# SCH_Rubik_2024-01-09.net
KiCad netlist of a schematic drawn in EasyEDA
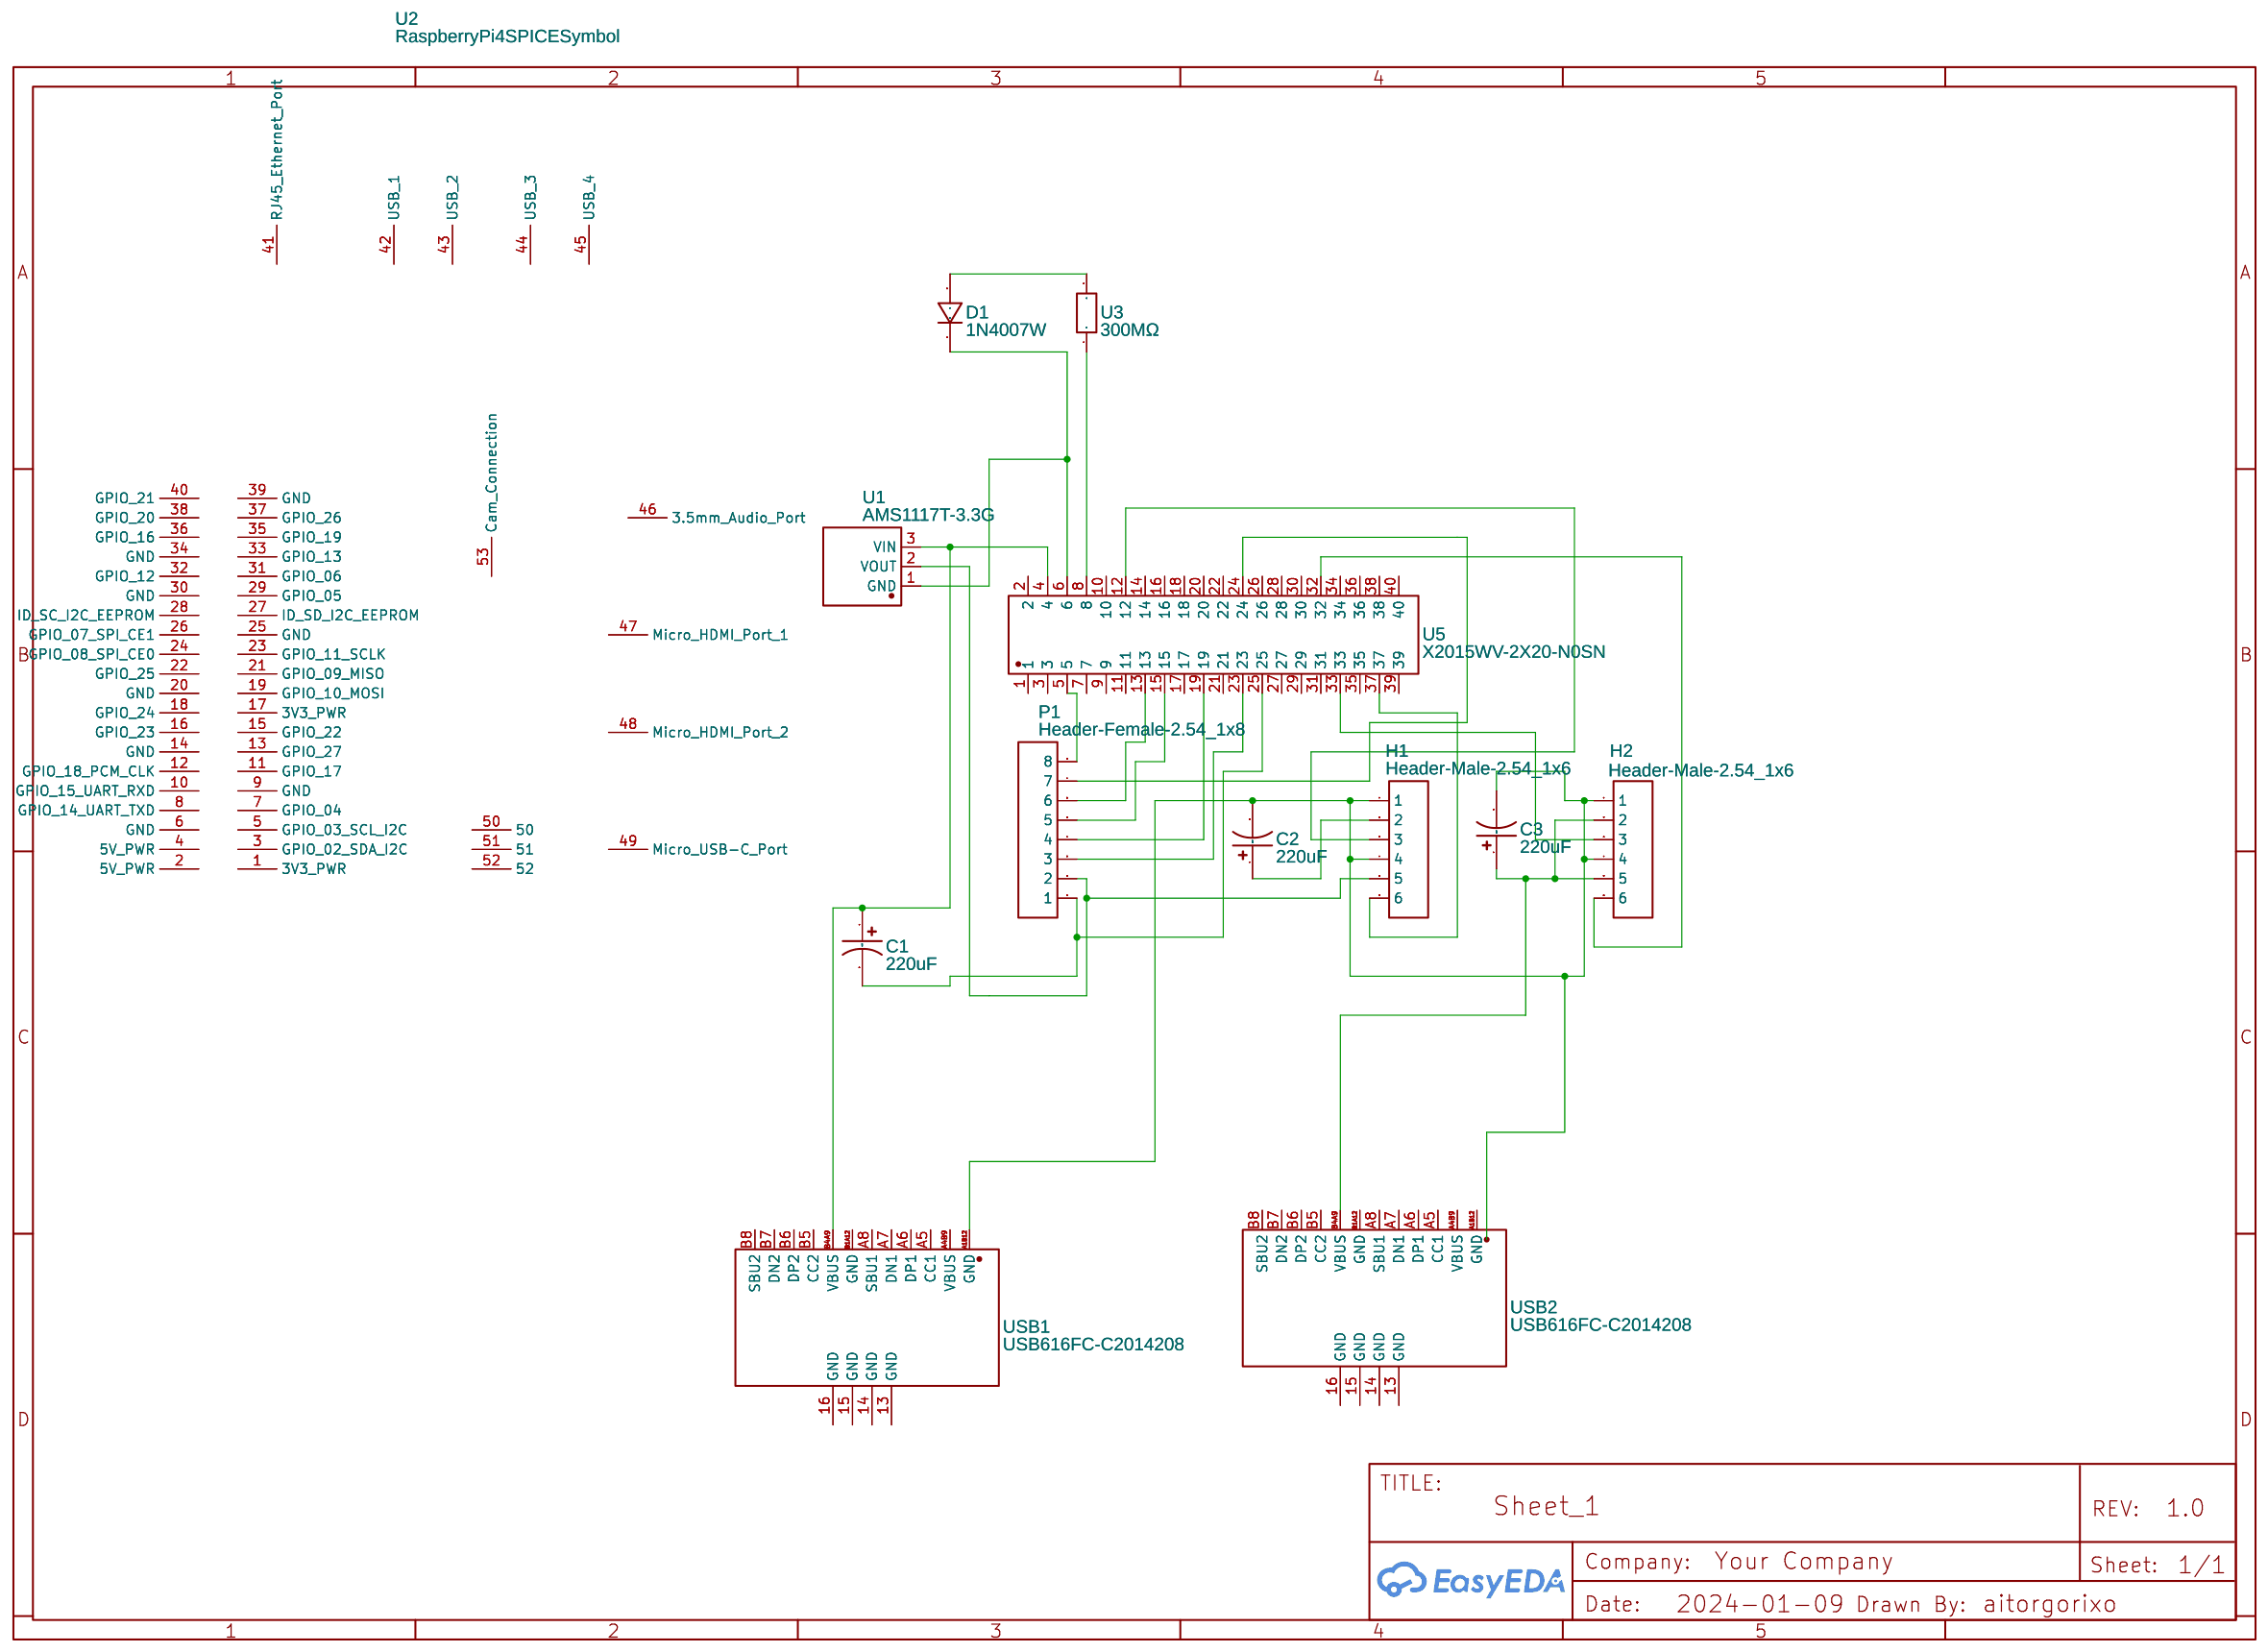
[diagram p0: schematic sheet]

(export (version "E")
  (design (tool "Eeschema 10.0.6"))
  (components
    (comp (ref "C1")
      (value "220uF")
      (fields
        (field (name "Manufacturer Part") "35YXG220MLLCT78X16")
        (field (name "Manufacturer") "rubycon(红宝石)")
      )
      (libsource (lib "") (part "35YXG220MLLCT78X16"))
    )
    (comp (ref "C2")
      (value "220uF")
      (fields
        (field (name "Manufacturer Part") "35YXG220MLLCT78X16")
        (field (name "Manufacturer") "rubycon(红宝石)")
      )
      (libsource (lib "") (part "35YXG220MLLCT78X16_1"))
    )
    (comp (ref "C3")
      (value "220uF")
      (fields
        (field (name "Manufacturer Part") "35YXG220MLLCT78X16")
        (field (name "Manufacturer") "rubycon(红宝石)")
      )
      (libsource (lib "") (part "35YXG220MLLCT78X16_1"))
    )
    (comp (ref "D1")
      (value "1N4007W")
      (fields (field (name "Manufacturer") "BLUE ROCKET"))
      (libsource (lib "") (part "1N4007W"))
    )
    (comp (ref "H1")
      (value "Header-Male-2.54_1x6")
      (fields (field (name "Manufacturer Part") "2.54-1x6P直针") (field (name "Manufacturer") "BOOMELE(博穆精密)"))
      (libsource (lib "") (part "Header-Male-2.54_1x6"))
    )
    (comp (ref "H2")
      (value "Header-Male-2.54_1x6")
      (fields (field (name "Manufacturer Part") "2.54-1x6P直针") (field (name "Manufacturer") "BOOMELE(博穆精密)"))
      (libsource (lib "") (part "Header-Male-2.54_1x6"))
    )
    (comp (ref "P1")
      (value "Header-Female-2.54_1x8")
      (fields (field (name "Manufacturer Part") "2.54-1*8P母环保") (field (name "Manufacturer") "BOOMELE(博穆精密)"))
      (libsource (lib "") (part "Header-Female-2.54_1x8"))
    )
    (comp (ref "U1")
      (value "AMS1117T-3.3G")
      (fields (field (name "Manufacturer") "HGC(深圳汉芯)"))
      (libsource (lib "") (part "AMS1117T-3.3G"))
    )
    (comp (ref "U2") (value "RaspberryPi4SPICESymbol") (libsource (lib "") (part "RaspberryPi4SPICESymbol")))
    (comp (ref "U3")
      (value "300MΩ")
      (fields
        (field (name "Manufacturer Part") "WW12JTR300")
        (field (name "Manufacturer") "SEI(Stackpole Electronics Inc.)")
      )
      (libsource (lib "") (part "WW12JTR300"))
    )
    (comp (ref "U5")
      (value "X2015WV-2X20-N0SN")
      (fields
        (field (name "Manufacturer Part") "X2015WV-2x20-46SN")
        (field (name "Manufacturer") "XKB Connectivity(中国星坤)")
      )
      (libsource (lib "") (part "X2015WV-2X20-N0SN"))
    )
    (comp (ref "USB1")
      (value "USB616FC-C2014208")
      (fields (field (name "Manufacturer") "ATOM(爱特姆)"))
      (libsource (lib "") (part "USB616FC-C2014208"))
    )
    (comp (ref "USB2")
      (value "USB616FC-C2014208")
      (fields (field (name "Manufacturer") "ATOM(爱特姆)"))
      (libsource (lib "") (part "USB616FC-C2014208"))
    )
  )
  (nets
    (net (code "1") (name "Net-(C1-Pad2)") (class "Default")
      (node (ref "C1") (pin "2") (pinfunction "2_2") (pintype "unspecified"))
      (node (ref "P1") (pin "1") (pinfunction "1_1") (pintype "input"))
      (node (ref "U5") (pin "25") (pinfunction "25_25") (pintype "unspecified"))
    )
    (net (code "2") (name "Net-(C2-Pad1)") (class "Default")
      (node (ref "C2") (pin "1") (pinfunction "1_1") (pintype "unspecified"))
      (node (ref "H1") (pin "2") (pinfunction "2_2") (pintype "input"))
    )
    (net (code "3") (name "Net-(C2-Pad2)") (class "Default")
      (node (ref "C2") (pin "2") (pinfunction "2_2") (pintype "unspecified"))
      (node (ref "C3") (pin "2") (pinfunction "2_2") (pintype "unspecified"))
      (node (ref "H1") (pin "1") (pinfunction "1_1") (pintype "input"))
      (node (ref "H1") (pin "4") (pinfunction "4_4") (pintype "input"))
      (node (ref "H2") (pin "1") (pinfunction "1_1") (pintype "input"))
      (node (ref "H2") (pin "4") (pinfunction "4_4") (pintype "input"))
      (node (ref "USB1") (pin "A1B12") (pinfunction "GND_A1B12") (pintype "unspecified"))
    )
    (net (code "4") (name "Net-(C3-Pad1)") (class "Default")
      (node (ref "C3") (pin "1") (pinfunction "1_1") (pintype "unspecified"))
      (node (ref "H2") (pin "2") (pinfunction "2_2") (pintype "input"))
      (node (ref "H2") (pin "5") (pinfunction "5_5") (pintype "input"))
      (node (ref "USB2") (pin "B4A9") (pinfunction "VBUS_B4A9") (pintype "unspecified"))
    )
    (net (code "5") (name "Net-(D1-Pad2)") (class "Default")
      (node (ref "D1") (pin "2") (pinfunction "2_2") (pintype "unspecified"))
      (node (ref "U3") (pin "2") (pinfunction "2_2") (pintype "unspecified"))
    )
    (net (code "6") (name "Net-(H1-Pad3)") (class "Default")
      (node (ref "H1") (pin "3") (pinfunction "3_3") (pintype "input"))
      (node (ref "U5") (pin "12") (pinfunction "12_12") (pintype "unspecified"))
    )
    (net (code "7") (name "Net-(H1-Pad6)") (class "Default")
      (node (ref "H1") (pin "6") (pinfunction "6_6") (pintype "input"))
      (node (ref "U5") (pin "37") (pinfunction "37_37") (pintype "unspecified"))
    )
    (net (code "8") (name "Net-(H2-Pad3)") (class "Default")
      (node (ref "H2") (pin "3") (pinfunction "3_3") (pintype "input"))
      (node (ref "U5") (pin "33") (pinfunction "33_33") (pintype "unspecified"))
    )
    (net (code "9") (name "Net-(H2-Pad6)") (class "Default")
      (node (ref "H2") (pin "6") (pinfunction "6_6") (pintype "input"))
      (node (ref "U5") (pin "32") (pinfunction "32_32") (pintype "unspecified"))
    )
    (net (code "10") (name "Net-(P1-Pad3)") (class "Default")
      (node (ref "P1") (pin "3") (pinfunction "3_3") (pintype "input"))
      (node (ref "U5") (pin "23") (pinfunction "23_23") (pintype "unspecified"))
    )
    (net (code "11") (name "Net-(P1-Pad4)") (class "Default")
      (node (ref "P1") (pin "4") (pinfunction "4_4") (pintype "input"))
      (node (ref "U5") (pin "19") (pinfunction "19_19") (pintype "unspecified"))
    )
    (net (code "12") (name "Net-(P1-Pad5)") (class "Default")
      (node (ref "P1") (pin "5") (pinfunction "5_5") (pintype "input"))
      (node (ref "U5") (pin "15") (pinfunction "15_15") (pintype "unspecified"))
    )
    (net (code "13") (name "Net-(P1-Pad6)") (class "Default")
      (node (ref "P1") (pin "6") (pinfunction "6_6") (pintype "input"))
      (node (ref "U5") (pin "13") (pinfunction "13_13") (pintype "unspecified"))
    )
    (net (code "14") (name "Net-(P1-Pad7)") (class "Default")
      (node (ref "P1") (pin "7") (pinfunction "7_7") (pintype "input"))
      (node (ref "U5") (pin "24") (pinfunction "24_24") (pintype "unspecified"))
    )
    (net (code "15") (name "Net-(P1-Pad8)") (class "Default")
      (node (ref "P1") (pin "8") (pinfunction "8_8") (pintype "input"))
      (node (ref "U5") (pin "5") (pinfunction "5_5") (pintype "unspecified"))
    )
    (net (code "16") (name "Net-(U1-GND)") (class "Default")
      (node (ref "D1") (pin "1") (pinfunction "1_1") (pintype "unspecified"))
      (node (ref "U1") (pin "1") (pinfunction "GND_1") (pintype "unspecified"))
      (node (ref "U5") (pin "6") (pinfunction "6_6") (pintype "unspecified"))
    )
    (net (code "17") (name "Net-(U1-VIN)") (class "Default")
      (node (ref "C1") (pin "1") (pinfunction "1_1") (pintype "unspecified"))
      (node (ref "U1") (pin "3") (pinfunction "VIN_3") (pintype "unspecified"))
      (node (ref "U5") (pin "4") (pinfunction "4_4") (pintype "unspecified"))
      (node (ref "USB1") (pin "B4A9") (pinfunction "VBUS_B4A9") (pintype "unspecified"))
    )
    (net (code "18") (name "Net-(U1-VOUT)") (class "Default")
      (node (ref "H1") (pin "5") (pinfunction "5_5") (pintype "input"))
      (node (ref "P1") (pin "2") (pinfunction "2_2") (pintype "input"))
      (node (ref "U1") (pin "2") (pinfunction "VOUT_2") (pintype "unspecified"))
    )
    (net (code "19") (name "Net-(U3-Pad1)") (class "Default")
      (node (ref "U3") (pin "1") (pinfunction "1_1") (pintype "unspecified"))
      (node (ref "U5") (pin "8") (pinfunction "8_8") (pintype "unspecified"))
    )
    (net (code "20") (name "unconnected-(U2-3.5mm_Audio_Port-Pad46)") (class "Default")
      (node (ref "U2") (pin "46") (pinfunction "3.5mm_Audio_Port_46") (pintype "unspecified"))
    )
    (net (code "21") (name "unconnected-(U2-3V3_PWR-Pad1)") (class "Default")
      (node (ref "U2") (pin "1") (pinfunction "3V3_PWR_1") (pintype "unspecified"))
    )
    (net (code "22") (name "unconnected-(U2-3V3_PWR-Pad17)") (class "Default")
      (node (ref "U2") (pin "17") (pinfunction "3V3_PWR_17") (pintype "unspecified"))
    )
    (net (code "23") (name "unconnected-(U2-5V_PWR-Pad2)") (class "Default")
      (node (ref "U2") (pin "2") (pinfunction "5V_PWR_2") (pintype "unspecified"))
    )
    (net (code "24") (name "unconnected-(U2-5V_PWR-Pad4)") (class "Default")
      (node (ref "U2") (pin "4") (pinfunction "5V_PWR_4") (pintype "unspecified"))
    )
    (net (code "25") (name "unconnected-(U2-Cam_Connection-Pad53)") (class "Default")
      (node (ref "U2") (pin "53") (pinfunction "Cam_Connection_53") (pintype "unspecified"))
    )
    (net (code "26") (name "unconnected-(U2-GND-Pad6)") (class "Default")
      (node (ref "U2") (pin "6") (pinfunction "GND_6") (pintype "unspecified"))
    )
    (net (code "27") (name "unconnected-(U2-GND-Pad9)") (class "Default")
      (node (ref "U2") (pin "9") (pinfunction "GND_9") (pintype "unspecified"))
    )
    (net (code "28") (name "unconnected-(U2-GND-Pad14)") (class "Default")
      (node (ref "U2") (pin "14") (pinfunction "GND_14") (pintype "unspecified"))
    )
    (net (code "29") (name "unconnected-(U2-GND-Pad20)") (class "Default")
      (node (ref "U2") (pin "20") (pinfunction "GND_20") (pintype "unspecified"))
    )
    (net (code "30") (name "unconnected-(U2-GND-Pad25)") (class "Default")
      (node (ref "U2") (pin "25") (pinfunction "GND_25") (pintype "unspecified"))
    )
    (net (code "31") (name "unconnected-(U2-GND-Pad30)") (class "Default")
      (node (ref "U2") (pin "30") (pinfunction "GND_30") (pintype "unspecified"))
    )
    (net (code "32") (name "unconnected-(U2-GND-Pad34)") (class "Default")
      (node (ref "U2") (pin "34") (pinfunction "GND_34") (pintype "unspecified"))
    )
    (net (code "33") (name "unconnected-(U2-GND-Pad39)") (class "Default")
      (node (ref "U2") (pin "39") (pinfunction "GND_39") (pintype "unspecified"))
    )
    (net (code "34") (name "unconnected-(U2-GPIO_02_SDA_I2C-Pad3)") (class "Default")
      (node (ref "U2") (pin "3") (pinfunction "GPIO_02_SDA_I2C_3") (pintype "unspecified"))
    )
    (net (code "35") (name "unconnected-(U2-GPIO_03_SCL_I2C-Pad5)") (class "Default")
      (node (ref "U2") (pin "5") (pinfunction "GPIO_03_SCL_I2C_5") (pintype "unspecified"))
    )
    (net (code "36") (name "unconnected-(U2-GPIO_04-Pad7)") (class "Default")
      (node (ref "U2") (pin "7") (pinfunction "GPIO_04_7") (pintype "unspecified"))
    )
    (net (code "37") (name "unconnected-(U2-GPIO_05-Pad29)") (class "Default")
      (node (ref "U2") (pin "29") (pinfunction "GPIO_05_29") (pintype "unspecified"))
    )
    (net (code "38") (name "unconnected-(U2-GPIO_06-Pad31)") (class "Default")
      (node (ref "U2") (pin "31") (pinfunction "GPIO_06_31") (pintype "unspecified"))
    )
    (net (code "39") (name "unconnected-(U2-GPIO_07_SPI_CE1-Pad26)") (class "Default")
      (node (ref "U2") (pin "26") (pinfunction "GPIO_07_SPI_CE1_26") (pintype "unspecified"))
    )
    (net (code "40") (name "unconnected-(U2-GPIO_08_SPI_CE0-Pad24)") (class "Default")
      (node (ref "U2") (pin "24") (pinfunction "GPIO_08_SPI_CE0_24") (pintype "unspecified"))
    )
    (net (code "41") (name "unconnected-(U2-GPIO_09_MISO-Pad21)") (class "Default")
      (node (ref "U2") (pin "21") (pinfunction "GPIO_09_MISO_21") (pintype "unspecified"))
    )
    (net (code "42") (name "unconnected-(U2-GPIO_10_MOSI-Pad19)") (class "Default")
      (node (ref "U2") (pin "19") (pinfunction "GPIO_10_MOSI_19") (pintype "unspecified"))
    )
    (net (code "43") (name "unconnected-(U2-GPIO_11_SCLK-Pad23)") (class "Default")
      (node (ref "U2") (pin "23") (pinfunction "GPIO_11_SCLK_23") (pintype "unspecified"))
    )
    (net (code "44") (name "unconnected-(U2-GPIO_12-Pad32)") (class "Default")
      (node (ref "U2") (pin "32") (pinfunction "GPIO_12_32") (pintype "unspecified"))
    )
    (net (code "45") (name "unconnected-(U2-GPIO_13-Pad33)") (class "Default")
      (node (ref "U2") (pin "33") (pinfunction "GPIO_13_33") (pintype "unspecified"))
    )
    (net (code "46") (name "unconnected-(U2-GPIO_14_UART_TXD-Pad8)") (class "Default")
      (node (ref "U2") (pin "8") (pinfunction "GPIO_14_UART_TXD_8") (pintype "unspecified"))
    )
    (net (code "47") (name "unconnected-(U2-GPIO_15_UART_RXD-Pad10)") (class "Default")
      (node (ref "U2") (pin "10") (pinfunction "GPIO_15_UART_RXD_10") (pintype "unspecified"))
    )
    (net (code "48") (name "unconnected-(U2-GPIO_16-Pad36)") (class "Default")
      (node (ref "U2") (pin "36") (pinfunction "GPIO_16_36") (pintype "unspecified"))
    )
    (net (code "49") (name "unconnected-(U2-GPIO_17-Pad11)") (class "Default")
      (node (ref "U2") (pin "11") (pinfunction "GPIO_17_11") (pintype "unspecified"))
    )
    (net (code "50") (name "unconnected-(U2-GPIO_18_PCM_CLK-Pad12)") (class "Default")
      (node (ref "U2") (pin "12") (pinfunction "GPIO_18_PCM_CLK_12") (pintype "unspecified"))
    )
    (net (code "51") (name "unconnected-(U2-GPIO_19-Pad35)") (class "Default")
      (node (ref "U2") (pin "35") (pinfunction "GPIO_19_35") (pintype "unspecified"))
    )
    (net (code "52") (name "unconnected-(U2-GPIO_20-Pad38)") (class "Default")
      (node (ref "U2") (pin "38") (pinfunction "GPIO_20_38") (pintype "unspecified"))
    )
    (net (code "53") (name "unconnected-(U2-GPIO_21-Pad40)") (class "Default")
      (node (ref "U2") (pin "40") (pinfunction "GPIO_21_40") (pintype "unspecified"))
    )
    (net (code "54") (name "unconnected-(U2-GPIO_22-Pad15)") (class "Default")
      (node (ref "U2") (pin "15") (pinfunction "GPIO_22_15") (pintype "unspecified"))
    )
    (net (code "55") (name "unconnected-(U2-GPIO_23-Pad16)") (class "Default")
      (node (ref "U2") (pin "16") (pinfunction "GPIO_23_16") (pintype "unspecified"))
    )
    (net (code "56") (name "unconnected-(U2-GPIO_24-Pad18)") (class "Default")
      (node (ref "U2") (pin "18") (pinfunction "GPIO_24_18") (pintype "unspecified"))
    )
    (net (code "57") (name "unconnected-(U2-GPIO_25-Pad22)") (class "Default")
      (node (ref "U2") (pin "22") (pinfunction "GPIO_25_22") (pintype "unspecified"))
    )
    (net (code "58") (name "unconnected-(U2-GPIO_26-Pad37)") (class "Default")
      (node (ref "U2") (pin "37") (pinfunction "GPIO_26_37") (pintype "unspecified"))
    )
    (net (code "59") (name "unconnected-(U2-GPIO_27-Pad13)") (class "Default")
      (node (ref "U2") (pin "13") (pinfunction "GPIO_27_13") (pintype "unspecified"))
    )
    (net (code "60") (name "unconnected-(U2-ID_SC_I2C_EEPROM-Pad28)") (class "Default")
      (node (ref "U2") (pin "28") (pinfunction "ID_SC_I2C_EEPROM_28") (pintype "unspecified"))
    )
    (net (code "61") (name "unconnected-(U2-ID_SD_I2C_EEPROM-Pad27)") (class "Default")
      (node (ref "U2") (pin "27") (pinfunction "ID_SD_I2C_EEPROM_27") (pintype "unspecified"))
    )
    (net (code "62") (name "unconnected-(U2-Micro_HDMI_Port_1-Pad47)") (class "Default")
      (node (ref "U2") (pin "47") (pinfunction "Micro_HDMI_Port_1_47") (pintype "unspecified"))
    )
    (net (code "63") (name "unconnected-(U2-Micro_HDMI_Port_2-Pad48)") (class "Default")
      (node (ref "U2") (pin "48") (pinfunction "Micro_HDMI_Port_2_48") (pintype "unspecified"))
    )
    (net (code "64") (name "unconnected-(U2-Micro_USB-C_Port-Pad49)") (class "Default")
      (node (ref "U2") (pin "49") (pinfunction "Micro_USB-C_Port_49") (pintype "unspecified"))
    )
    (net (code "65") (name "unconnected-(U2-Pad50)") (class "Default")
      (node (ref "U2") (pin "50") (pinfunction "50_50") (pintype "unspecified"))
    )
    (net (code "66") (name "unconnected-(U2-Pad51)") (class "Default")
      (node (ref "U2") (pin "51") (pinfunction "51_51") (pintype "unspecified"))
    )
    (net (code "67") (name "unconnected-(U2-Pad52)") (class "Default")
      (node (ref "U2") (pin "52") (pinfunction "52_52") (pintype "unspecified"))
    )
    (net (code "68") (name "unconnected-(U2-RJ45_Ethernet_Port-Pad41)") (class "Default")
      (node (ref "U2") (pin "41") (pinfunction "RJ45_Ethernet_Port_41") (pintype "unspecified"))
    )
    (net (code "69") (name "unconnected-(U2-USB_1-Pad42)") (class "Default")
      (node (ref "U2") (pin "42") (pinfunction "USB_1_42") (pintype "unspecified"))
    )
    (net (code "70") (name "unconnected-(U2-USB_2-Pad43)") (class "Default")
      (node (ref "U2") (pin "43") (pinfunction "USB_2_43") (pintype "unspecified"))
    )
    (net (code "71") (name "unconnected-(U2-USB_3-Pad44)") (class "Default")
      (node (ref "U2") (pin "44") (pinfunction "USB_3_44") (pintype "unspecified"))
    )
    (net (code "72") (name "unconnected-(U2-USB_4-Pad45)") (class "Default")
      (node (ref "U2") (pin "45") (pinfunction "USB_4_45") (pintype "unspecified"))
    )
    (net (code "73") (name "unconnected-(U5-Pad1)") (class "Default")
      (node (ref "U5") (pin "1") (pinfunction "1_1") (pintype "unspecified"))
    )
    (net (code "74") (name "unconnected-(U5-Pad2)") (class "Default")
      (node (ref "U5") (pin "2") (pinfunction "2_2") (pintype "unspecified"))
    )
    (net (code "75") (name "unconnected-(U5-Pad3)") (class "Default")
      (node (ref "U5") (pin "3") (pinfunction "3_3") (pintype "unspecified"))
    )
    (net (code "76") (name "unconnected-(U5-Pad7)") (class "Default")
      (node (ref "U5") (pin "7") (pinfunction "7_7") (pintype "unspecified"))
    )
    (net (code "77") (name "unconnected-(U5-Pad9)") (class "Default")
      (node (ref "U5") (pin "9") (pinfunction "9_9") (pintype "unspecified"))
    )
    (net (code "78") (name "unconnected-(U5-Pad10)") (class "Default")
      (node (ref "U5") (pin "10") (pinfunction "10_10") (pintype "unspecified"))
    )
    (net (code "79") (name "unconnected-(U5-Pad11)") (class "Default")
      (node (ref "U5") (pin "11") (pinfunction "11_11") (pintype "unspecified"))
    )
    (net (code "80") (name "unconnected-(U5-Pad14)") (class "Default")
      (node (ref "U5") (pin "14") (pinfunction "14_14") (pintype "unspecified"))
    )
    (net (code "81") (name "unconnected-(U5-Pad16)") (class "Default")
      (node (ref "U5") (pin "16") (pinfunction "16_16") (pintype "unspecified"))
    )
    (net (code "82") (name "unconnected-(U5-Pad17)") (class "Default")
      (node (ref "U5") (pin "17") (pinfunction "17_17") (pintype "unspecified"))
    )
    (net (code "83") (name "unconnected-(U5-Pad18)") (class "Default")
      (node (ref "U5") (pin "18") (pinfunction "18_18") (pintype "unspecified"))
    )
    (net (code "84") (name "unconnected-(U5-Pad20)") (class "Default")
      (node (ref "U5") (pin "20") (pinfunction "20_20") (pintype "unspecified"))
    )
    (net (code "85") (name "unconnected-(U5-Pad21)") (class "Default")
      (node (ref "U5") (pin "21") (pinfunction "21_21") (pintype "unspecified"))
    )
    (net (code "86") (name "unconnected-(U5-Pad22)") (class "Default")
      (node (ref "U5") (pin "22") (pinfunction "22_22") (pintype "unspecified"))
    )
    (net (code "87") (name "unconnected-(U5-Pad26)") (class "Default")
      (node (ref "U5") (pin "26") (pinfunction "26_26") (pintype "unspecified"))
    )
    (net (code "88") (name "unconnected-(U5-Pad27)") (class "Default")
      (node (ref "U5") (pin "27") (pinfunction "27_27") (pintype "unspecified"))
    )
    (net (code "89") (name "unconnected-(U5-Pad28)") (class "Default")
      (node (ref "U5") (pin "28") (pinfunction "28_28") (pintype "unspecified"))
    )
    (net (code "90") (name "unconnected-(U5-Pad29)") (class "Default")
      (node (ref "U5") (pin "29") (pinfunction "29_29") (pintype "unspecified"))
    )
    (net (code "91") (name "unconnected-(U5-Pad30)") (class "Default")
      (node (ref "U5") (pin "30") (pinfunction "30_30") (pintype "unspecified"))
    )
    (net (code "92") (name "unconnected-(U5-Pad31)") (class "Default")
      (node (ref "U5") (pin "31") (pinfunction "31_31") (pintype "unspecified"))
    )
    (net (code "93") (name "unconnected-(U5-Pad34)") (class "Default")
      (node (ref "U5") (pin "34") (pinfunction "34_34") (pintype "unspecified"))
    )
    (net (code "94") (name "unconnected-(U5-Pad35)") (class "Default")
      (node (ref "U5") (pin "35") (pinfunction "35_35") (pintype "unspecified"))
    )
    (net (code "95") (name "unconnected-(U5-Pad36)") (class "Default")
      (node (ref "U5") (pin "36") (pinfunction "36_36") (pintype "unspecified"))
    )
    (net (code "96") (name "unconnected-(U5-Pad38)") (class "Default")
      (node (ref "U5") (pin "38") (pinfunction "38_38") (pintype "unspecified"))
    )
    (net (code "97") (name "unconnected-(U5-Pad39)") (class "Default")
      (node (ref "U5") (pin "39") (pinfunction "39_39") (pintype "unspecified"))
    )
    (net (code "98") (name "unconnected-(U5-Pad40)") (class "Default")
      (node (ref "U5") (pin "40") (pinfunction "40_40") (pintype "unspecified"))
    )
    (net (code "99") (name "unconnected-(USB1-CC1-PadA5)") (class "Default")
      (node (ref "USB1") (pin "A5") (pinfunction "CC1_A5") (pintype "unspecified"))
    )
    (net (code "100") (name "unconnected-(USB1-CC2-PadB5)") (class "Default")
      (node (ref "USB1") (pin "B5") (pinfunction "CC2_B5") (pintype "unspecified"))
    )
    (net (code "101") (name "unconnected-(USB1-DN1-PadA7)") (class "Default")
      (node (ref "USB1") (pin "A7") (pinfunction "DN1_A7") (pintype "unspecified"))
    )
    (net (code "102") (name "unconnected-(USB1-DN2-PadB7)") (class "Default")
      (node (ref "USB1") (pin "B7") (pinfunction "DN2_B7") (pintype "unspecified"))
    )
    (net (code "103") (name "unconnected-(USB1-DP1-PadA6)") (class "Default")
      (node (ref "USB1") (pin "A6") (pinfunction "DP1_A6") (pintype "unspecified"))
    )
    (net (code "104") (name "unconnected-(USB1-DP2-PadB6)") (class "Default")
      (node (ref "USB1") (pin "B6") (pinfunction "DP2_B6") (pintype "unspecified"))
    )
    (net (code "105") (name "unconnected-(USB1-GND-Pad13)") (class "Default")
      (node (ref "USB1") (pin "13") (pinfunction "GND_13") (pintype "unspecified"))
    )
    (net (code "106") (name "unconnected-(USB1-GND-Pad14)") (class "Default")
      (node (ref "USB1") (pin "14") (pinfunction "GND_14") (pintype "unspecified"))
    )
    (net (code "107") (name "unconnected-(USB1-GND-Pad15)") (class "Default")
      (node (ref "USB1") (pin "15") (pinfunction "GND_15") (pintype "unspecified"))
    )
    (net (code "108") (name "unconnected-(USB1-GND-Pad16)") (class "Default")
      (node (ref "USB1") (pin "16") (pinfunction "GND_16") (pintype "unspecified"))
    )
    (net (code "109") (name "unconnected-(USB1-GND-PadB1A12)") (class "Default")
      (node (ref "USB1") (pin "B1A12") (pinfunction "GND_B1A12") (pintype "unspecified"))
    )
    (net (code "110") (name "unconnected-(USB1-SBU1-PadA8)") (class "Default")
      (node (ref "USB1") (pin "A8") (pinfunction "SBU1_A8") (pintype "unspecified"))
    )
    (net (code "111") (name "unconnected-(USB1-SBU2-PadB8)") (class "Default")
      (node (ref "USB1") (pin "B8") (pinfunction "SBU2_B8") (pintype "unspecified"))
    )
    (net (code "112") (name "unconnected-(USB1-VBUS-PadA4B9)") (class "Default")
      (node (ref "USB1") (pin "A4B9") (pinfunction "VBUS_A4B9") (pintype "unspecified"))
    )
    (net (code "113") (name "unconnected-(USB2-CC1-PadA5)") (class "Default")
      (node (ref "USB2") (pin "A5") (pinfunction "CC1_A5") (pintype "unspecified"))
    )
    (net (code "114") (name "unconnected-(USB2-CC2-PadB5)") (class "Default")
      (node (ref "USB2") (pin "B5") (pinfunction "CC2_B5") (pintype "unspecified"))
    )
    (net (code "115") (name "unconnected-(USB2-DN1-PadA7)") (class "Default")
      (node (ref "USB2") (pin "A7") (pinfunction "DN1_A7") (pintype "unspecified"))
    )
    (net (code "116") (name "unconnected-(USB2-DN2-PadB7)") (class "Default")
      (node (ref "USB2") (pin "B7") (pinfunction "DN2_B7") (pintype "unspecified"))
    )
    (net (code "117") (name "unconnected-(USB2-DP1-PadA6)") (class "Default")
      (node (ref "USB2") (pin "A6") (pinfunction "DP1_A6") (pintype "unspecified"))
    )
    (net (code "118") (name "unconnected-(USB2-DP2-PadB6)") (class "Default")
      (node (ref "USB2") (pin "B6") (pinfunction "DP2_B6") (pintype "unspecified"))
    )
    (net (code "119") (name "unconnected-(USB2-GND-Pad13)") (class "Default")
      (node (ref "USB2") (pin "13") (pinfunction "GND_13") (pintype "unspecified"))
    )
    (net (code "120") (name "unconnected-(USB2-GND-Pad14)") (class "Default")
      (node (ref "USB2") (pin "14") (pinfunction "GND_14") (pintype "unspecified"))
    )
    (net (code "121") (name "unconnected-(USB2-GND-Pad15)") (class "Default")
      (node (ref "USB2") (pin "15") (pinfunction "GND_15") (pintype "unspecified"))
    )
    (net (code "122") (name "unconnected-(USB2-GND-Pad16)") (class "Default")
      (node (ref "USB2") (pin "16") (pinfunction "GND_16") (pintype "unspecified"))
    )
    (net (code "123") (name "unconnected-(USB2-GND-PadA1B12)") (class "Default")
      (node (ref "USB2") (pin "A1B12") (pinfunction "GND_A1B12") (pintype "unspecified"))
    )
    (net (code "124") (name "unconnected-(USB2-GND-PadB1A12)") (class "Default")
      (node (ref "USB2") (pin "B1A12") (pinfunction "GND_B1A12") (pintype "unspecified"))
    )
    (net (code "125") (name "unconnected-(USB2-SBU1-PadA8)") (class "Default")
      (node (ref "USB2") (pin "A8") (pinfunction "SBU1_A8") (pintype "unspecified"))
    )
    (net (code "126") (name "unconnected-(USB2-SBU2-PadB8)") (class "Default")
      (node (ref "USB2") (pin "B8") (pinfunction "SBU2_B8") (pintype "unspecified"))
    )
    (net (code "127") (name "unconnected-(USB2-VBUS-PadA4B9)") (class "Default")
      (node (ref "USB2") (pin "A4B9") (pinfunction "VBUS_A4B9") (pintype "unspecified"))
    )
  )
)
